# SCH_Big_Knob.net
KiCad netlist of a schematic drawn in EasyEDA
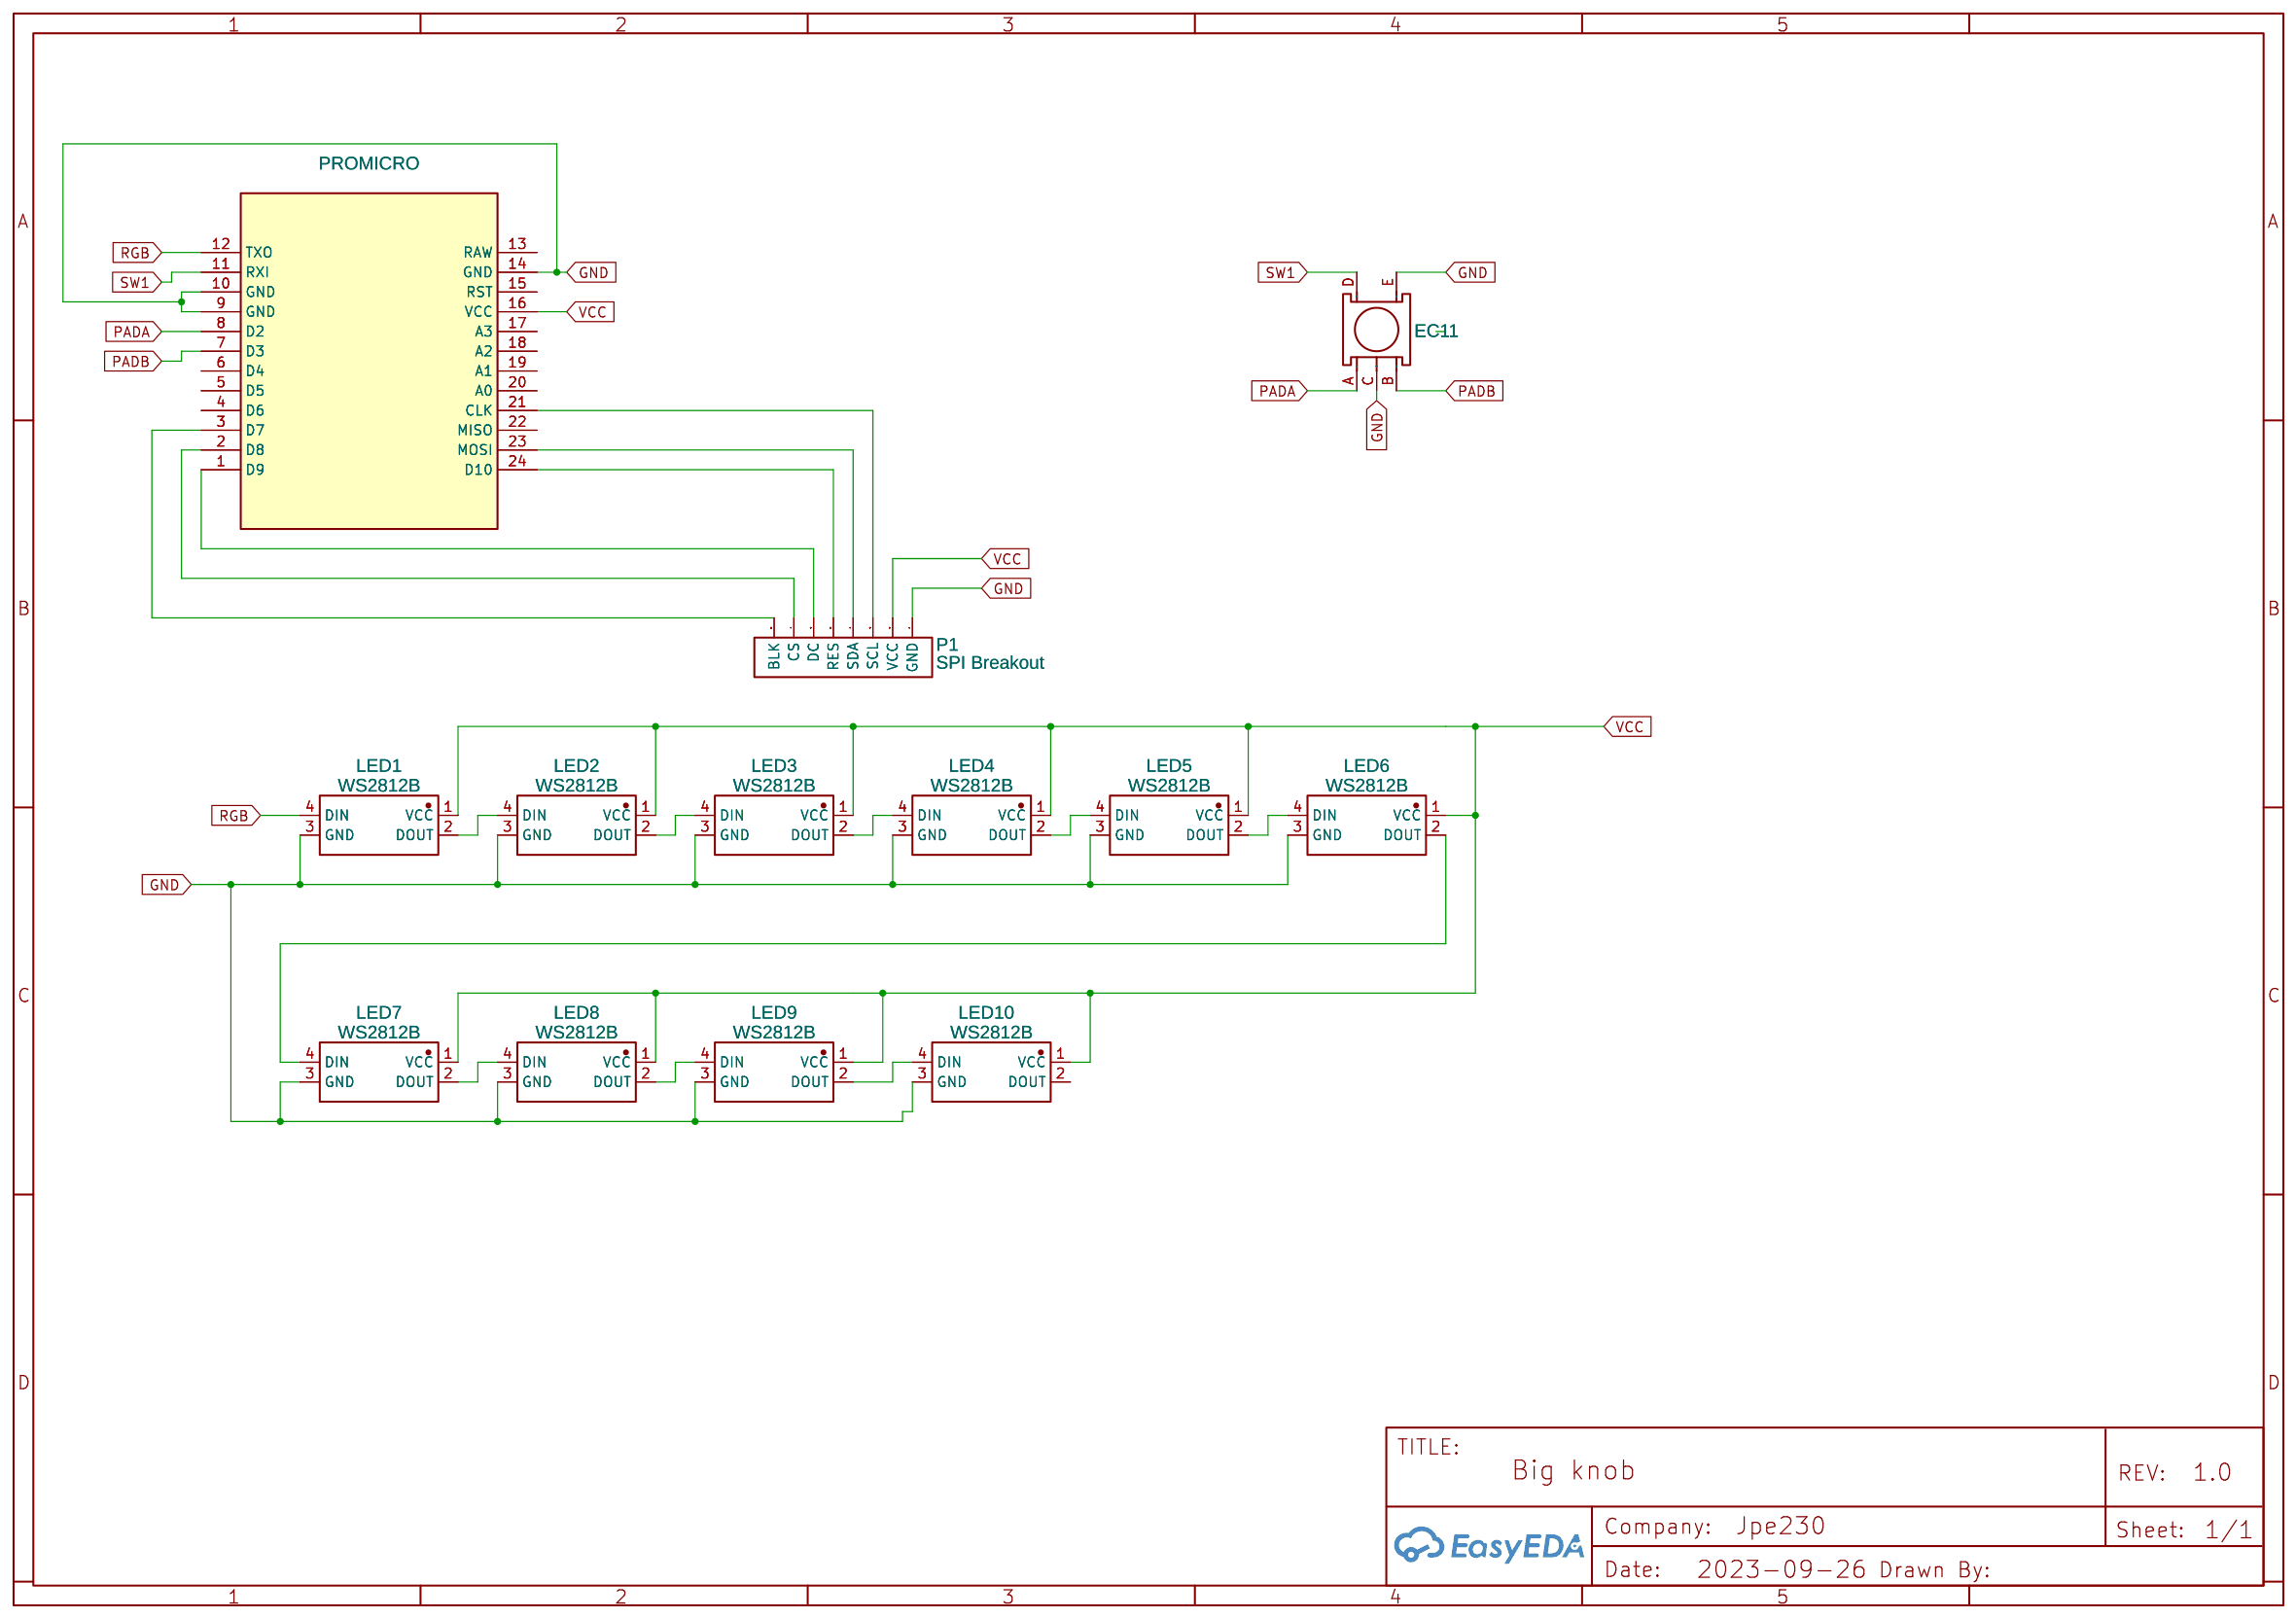
[diagram p0: schematic sheet]

(export (version "E")
  (design (tool "Eeschema 10.0.6"))
  (components
    (comp (ref "EC11")
      (value "NO")
      (fields
        (field (name "Manufacturer Part") "EC11E09204A4")
        (field (name "Manufacturer") "ALPSALPINE(阿尔卑斯阿尔派)")
      )
      (libsource (lib "") (part "EC11"))
    )
    (comp (ref "LED1")
      (value "WS2812B")
      (fields (field (name "Manufacturer Part") "5050WS2812B"))
      (libsource (lib "") (part "5050WS2812B"))
    )
    (comp (ref "LED2")
      (value "WS2812B")
      (fields (field (name "Manufacturer Part") "5050WS2812B"))
      (libsource (lib "") (part "5050WS2812B"))
    )
    (comp (ref "LED3")
      (value "WS2812B")
      (fields (field (name "Manufacturer Part") "5050WS2812B"))
      (libsource (lib "") (part "5050WS2812B"))
    )
    (comp (ref "LED4")
      (value "WS2812B")
      (fields (field (name "Manufacturer Part") "5050WS2812B"))
      (libsource (lib "") (part "5050WS2812B"))
    )
    (comp (ref "LED5")
      (value "WS2812B")
      (fields (field (name "Manufacturer Part") "5050WS2812B"))
      (libsource (lib "") (part "5050WS2812B"))
    )
    (comp (ref "LED6")
      (value "WS2812B")
      (fields (field (name "Manufacturer Part") "5050WS2812B"))
      (libsource (lib "") (part "5050WS2812B"))
    )
    (comp (ref "LED7")
      (value "WS2812B")
      (fields (field (name "Manufacturer Part") "5050WS2812B"))
      (libsource (lib "") (part "5050WS2812B"))
    )
    (comp (ref "LED8")
      (value "WS2812B")
      (fields (field (name "Manufacturer Part") "5050WS2812B"))
      (libsource (lib "") (part "5050WS2812B"))
    )
    (comp (ref "LED9")
      (value "WS2812B")
      (fields (field (name "Manufacturer Part") "5050WS2812B"))
      (libsource (lib "") (part "5050WS2812B"))
    )
    (comp (ref "LED10")
      (value "WS2812B")
      (fields (field (name "Manufacturer Part") "5050WS2812B"))
      (libsource (lib "") (part "5050WS2812B"))
    )
    (comp (ref "P1")
      (value "SPI Breakout")
      (fields (field (name "Manufacturer Part") "2.54-1*8P母环保") (field (name "Manufacturer") "BOOMELE(博穆精密)"))
      (libsource (lib "") (part "Header-Female-2.54_1x8"))
    )
    (comp (ref "PROMICRO") (value "NO") (libsource (lib "") (part "Pro Micro - 5V")))
  )
  (nets
    (net (code "1") (name "GND") (class "Default")
      (node (ref "EC11") (pin "C") (pinfunction "C_C") (pintype "unspecified"))
      (node (ref "EC11") (pin "E") (pinfunction "E_E") (pintype "unspecified"))
      (node (ref "LED1") (pin "3") (pinfunction "GND_3") (pintype "unspecified"))
      (node (ref "LED10") (pin "3") (pinfunction "GND_3") (pintype "unspecified"))
      (node (ref "LED2") (pin "3") (pinfunction "GND_3") (pintype "unspecified"))
      (node (ref "LED3") (pin "3") (pinfunction "GND_3") (pintype "unspecified"))
      (node (ref "LED4") (pin "3") (pinfunction "GND_3") (pintype "unspecified"))
      (node (ref "LED5") (pin "3") (pinfunction "GND_3") (pintype "unspecified"))
      (node (ref "LED6") (pin "3") (pinfunction "GND_3") (pintype "unspecified"))
      (node (ref "LED7") (pin "3") (pinfunction "GND_3") (pintype "unspecified"))
      (node (ref "LED8") (pin "3") (pinfunction "GND_3") (pintype "unspecified"))
      (node (ref "LED9") (pin "3") (pinfunction "GND_3") (pintype "unspecified"))
      (node (ref "P1") (pin "1") (pinfunction "GND_1") (pintype "input"))
      (node (ref "PROMICRO") (pin "10") (pinfunction "GND_10") (pintype "unspecified"))
      (node (ref "PROMICRO") (pin "14") (pinfunction "GND_14") (pintype "unspecified"))
      (node (ref "PROMICRO") (pin "9") (pinfunction "GND_9") (pintype "unspecified"))
    )
    (net (code "2") (name "Net-(LED1-DOUT)") (class "Default")
      (node (ref "LED1") (pin "2") (pinfunction "DOUT_2") (pintype "unspecified"))
      (node (ref "LED2") (pin "4") (pinfunction "DIN_4") (pintype "unspecified"))
    )
    (net (code "3") (name "Net-(LED2-DOUT)") (class "Default")
      (node (ref "LED2") (pin "2") (pinfunction "DOUT_2") (pintype "unspecified"))
      (node (ref "LED3") (pin "4") (pinfunction "DIN_4") (pintype "unspecified"))
    )
    (net (code "4") (name "Net-(LED3-DOUT)") (class "Default")
      (node (ref "LED3") (pin "2") (pinfunction "DOUT_2") (pintype "unspecified"))
      (node (ref "LED4") (pin "4") (pinfunction "DIN_4") (pintype "unspecified"))
    )
    (net (code "5") (name "Net-(LED4-DOUT)") (class "Default")
      (node (ref "LED4") (pin "2") (pinfunction "DOUT_2") (pintype "unspecified"))
      (node (ref "LED5") (pin "4") (pinfunction "DIN_4") (pintype "unspecified"))
    )
    (net (code "6") (name "Net-(LED5-DOUT)") (class "Default")
      (node (ref "LED5") (pin "2") (pinfunction "DOUT_2") (pintype "unspecified"))
      (node (ref "LED6") (pin "4") (pinfunction "DIN_4") (pintype "unspecified"))
    )
    (net (code "7") (name "Net-(LED6-DOUT)") (class "Default")
      (node (ref "LED6") (pin "2") (pinfunction "DOUT_2") (pintype "unspecified"))
      (node (ref "LED7") (pin "4") (pinfunction "DIN_4") (pintype "unspecified"))
    )
    (net (code "8") (name "Net-(LED7-DOUT)") (class "Default")
      (node (ref "LED7") (pin "2") (pinfunction "DOUT_2") (pintype "unspecified"))
      (node (ref "LED8") (pin "4") (pinfunction "DIN_4") (pintype "unspecified"))
    )
    (net (code "9") (name "Net-(LED8-DOUT)") (class "Default")
      (node (ref "LED8") (pin "2") (pinfunction "DOUT_2") (pintype "unspecified"))
      (node (ref "LED9") (pin "4") (pinfunction "DIN_4") (pintype "unspecified"))
    )
    (net (code "10") (name "Net-(LED10-DIN)") (class "Default")
      (node (ref "LED10") (pin "4") (pinfunction "DIN_4") (pintype "unspecified"))
      (node (ref "LED9") (pin "2") (pinfunction "DOUT_2") (pintype "unspecified"))
    )
    (net (code "11") (name "Net-(P1-BLK)") (class "Default")
      (node (ref "P1") (pin "8") (pinfunction "BLK_8") (pintype "input"))
      (node (ref "PROMICRO") (pin "3") (pinfunction "D7_3") (pintype "unspecified"))
    )
    (net (code "12") (name "Net-(P1-CS)") (class "Default")
      (node (ref "P1") (pin "7") (pinfunction "CS_7") (pintype "input"))
      (node (ref "PROMICRO") (pin "2") (pinfunction "D8_2") (pintype "unspecified"))
    )
    (net (code "13") (name "Net-(P1-DC)") (class "Default")
      (node (ref "P1") (pin "6") (pinfunction "DC_6") (pintype "input"))
      (node (ref "PROMICRO") (pin "1") (pinfunction "D9_1") (pintype "unspecified"))
    )
    (net (code "14") (name "Net-(P1-RES)") (class "Default")
      (node (ref "P1") (pin "5") (pinfunction "RES_5") (pintype "input"))
      (node (ref "PROMICRO") (pin "24") (pinfunction "D10_24") (pintype "unspecified"))
    )
    (net (code "15") (name "Net-(P1-SCL)") (class "Default")
      (node (ref "P1") (pin "3") (pinfunction "SCL_3") (pintype "input"))
      (node (ref "PROMICRO") (pin "21") (pinfunction "CLK_21") (pintype "unspecified"))
    )
    (net (code "16") (name "Net-(P1-SDA)") (class "Default")
      (node (ref "P1") (pin "4") (pinfunction "SDA_4") (pintype "input"))
      (node (ref "PROMICRO") (pin "23") (pinfunction "MOSI_23") (pintype "unspecified"))
    )
    (net (code "17") (name "PADA") (class "Default")
      (node (ref "EC11") (pin "A") (pinfunction "A_A") (pintype "unspecified"))
      (node (ref "PROMICRO") (pin "8") (pinfunction "D2_8") (pintype "unspecified"))
    )
    (net (code "18") (name "PADB") (class "Default")
      (node (ref "EC11") (pin "B") (pinfunction "B_B") (pintype "unspecified"))
      (node (ref "PROMICRO") (pin "7") (pinfunction "D3_7") (pintype "unspecified"))
    )
    (net (code "19") (name "RGB") (class "Default")
      (node (ref "LED1") (pin "4") (pinfunction "DIN_4") (pintype "unspecified"))
      (node (ref "PROMICRO") (pin "12") (pinfunction "TXO_12") (pintype "unspecified"))
    )
    (net (code "20") (name "SW1") (class "Default")
      (node (ref "EC11") (pin "D") (pinfunction "D_D") (pintype "unspecified"))
      (node (ref "PROMICRO") (pin "11") (pinfunction "RXI_11") (pintype "unspecified"))
    )
    (net (code "21") (name "VCC") (class "Default")
      (node (ref "LED1") (pin "1") (pinfunction "VCC_1") (pintype "unspecified"))
      (node (ref "LED10") (pin "1") (pinfunction "VCC_1") (pintype "unspecified"))
      (node (ref "LED2") (pin "1") (pinfunction "VCC_1") (pintype "unspecified"))
      (node (ref "LED3") (pin "1") (pinfunction "VCC_1") (pintype "unspecified"))
      (node (ref "LED4") (pin "1") (pinfunction "VCC_1") (pintype "unspecified"))
      (node (ref "LED5") (pin "1") (pinfunction "VCC_1") (pintype "unspecified"))
      (node (ref "LED6") (pin "1") (pinfunction "VCC_1") (pintype "unspecified"))
      (node (ref "LED7") (pin "1") (pinfunction "VCC_1") (pintype "unspecified"))
      (node (ref "LED8") (pin "1") (pinfunction "VCC_1") (pintype "unspecified"))
      (node (ref "LED9") (pin "1") (pinfunction "VCC_1") (pintype "unspecified"))
      (node (ref "P1") (pin "2") (pinfunction "VCC_2") (pintype "input"))
      (node (ref "PROMICRO") (pin "16") (pinfunction "VCC_16") (pintype "unspecified"))
    )
    (net (code "22") (name "unconnected-(LED10-DOUT-Pad2)") (class "Default")
      (node (ref "LED10") (pin "2") (pinfunction "DOUT_2") (pintype "unspecified"))
    )
    (net (code "23") (name "unconnected-(PROMICRO-A0-Pad20)") (class "Default")
      (node (ref "PROMICRO") (pin "20") (pinfunction "A0_20") (pintype "unspecified"))
    )
    (net (code "24") (name "unconnected-(PROMICRO-A1-Pad19)") (class "Default")
      (node (ref "PROMICRO") (pin "19") (pinfunction "A1_19") (pintype "unspecified"))
    )
    (net (code "25") (name "unconnected-(PROMICRO-A2-Pad18)") (class "Default")
      (node (ref "PROMICRO") (pin "18") (pinfunction "A2_18") (pintype "unspecified"))
    )
    (net (code "26") (name "unconnected-(PROMICRO-A3-Pad17)") (class "Default")
      (node (ref "PROMICRO") (pin "17") (pinfunction "A3_17") (pintype "unspecified"))
    )
    (net (code "27") (name "unconnected-(PROMICRO-D4-Pad6)") (class "Default")
      (node (ref "PROMICRO") (pin "6") (pinfunction "D4_6") (pintype "unspecified"))
    )
    (net (code "28") (name "unconnected-(PROMICRO-D5-Pad5)") (class "Default")
      (node (ref "PROMICRO") (pin "5") (pinfunction "D5_5") (pintype "unspecified"))
    )
    (net (code "29") (name "unconnected-(PROMICRO-D6-Pad4)") (class "Default")
      (node (ref "PROMICRO") (pin "4") (pinfunction "D6_4") (pintype "unspecified"))
    )
    (net (code "30") (name "unconnected-(PROMICRO-MISO-Pad22)") (class "Default")
      (node (ref "PROMICRO") (pin "22") (pinfunction "MISO_22") (pintype "unspecified"))
    )
    (net (code "31") (name "unconnected-(PROMICRO-RAW-Pad13)") (class "Default")
      (node (ref "PROMICRO") (pin "13") (pinfunction "RAW_13") (pintype "unspecified"))
    )
    (net (code "32") (name "unconnected-(PROMICRO-RST-Pad15)") (class "Default")
      (node (ref "PROMICRO") (pin "15") (pinfunction "RST_15") (pintype "unspecified"))
    )
  )
)
